# Power.net
KiCad netlist of a schematic drawn in Altium Designer
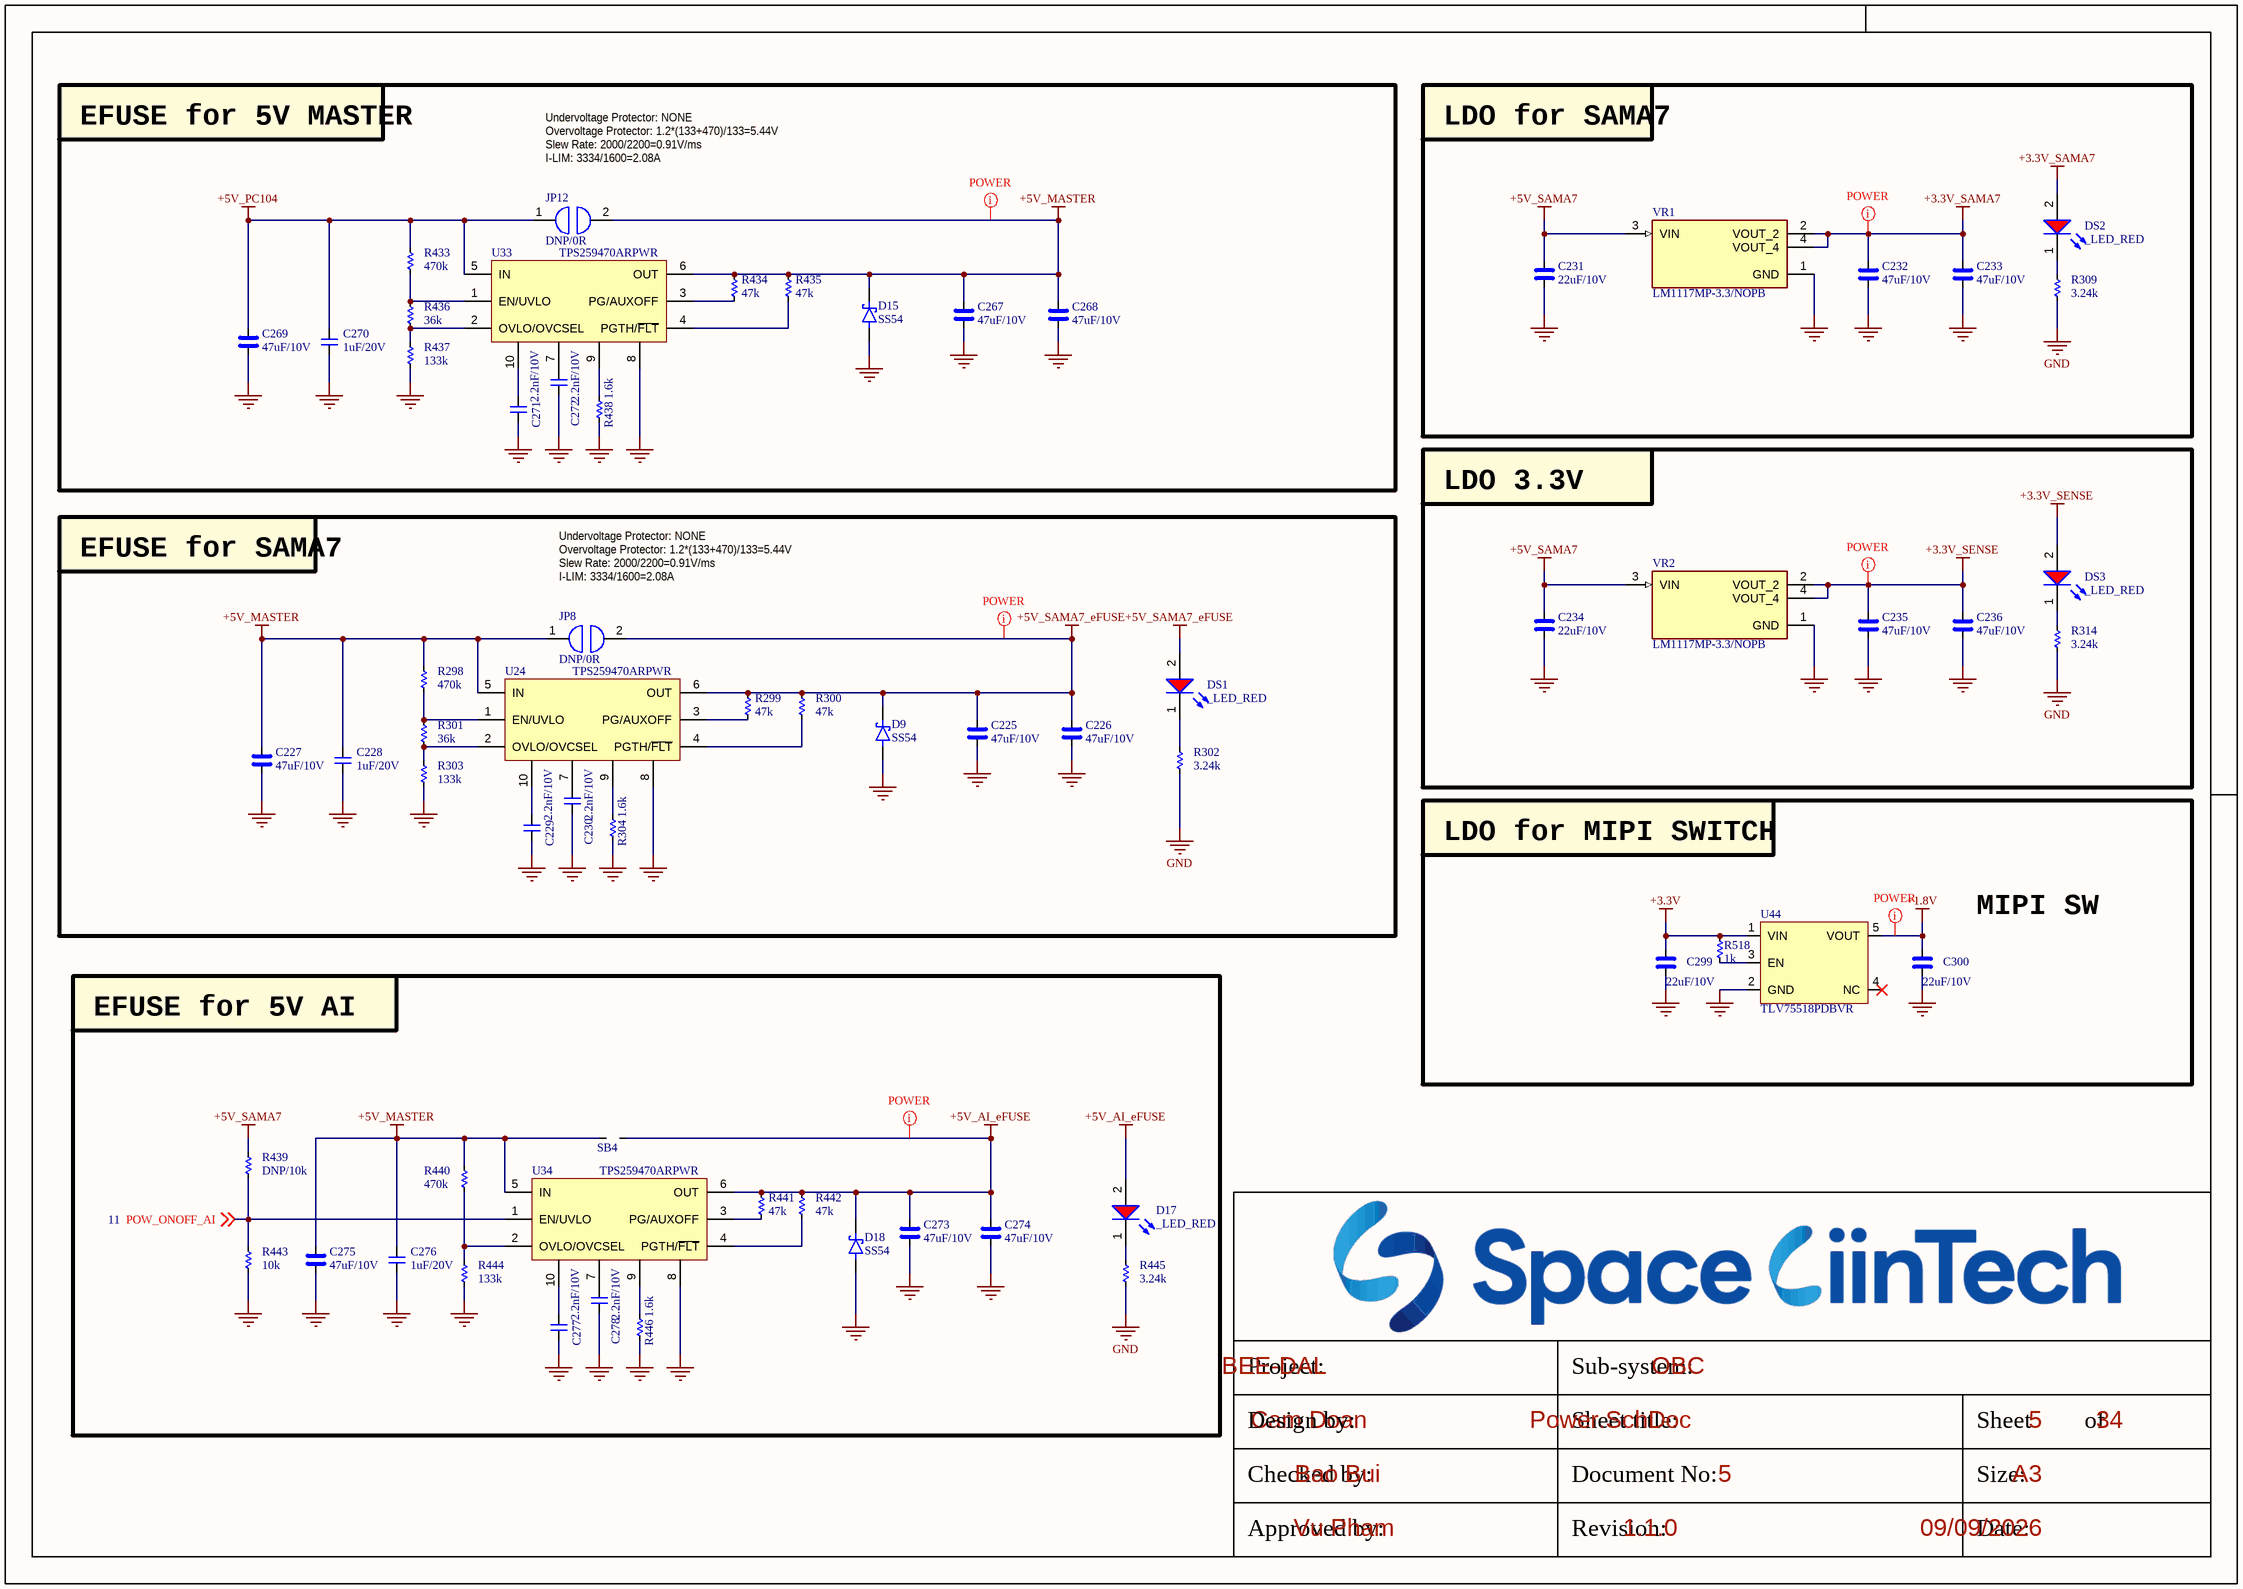
[diagram p0: Power.SchDoc]

(export (version "E")
  (design (tool "Eeschema 10.0.6"))
  (components
    (comp (ref "C225")
      (value "47uF/10V")
      (footprint "CAP_C_3225X80")
      (description "CAP High Value")
      (libsource (lib "LABLIB") (part "_CAP_C_High_2"))
    )
    (comp (ref "C226")
      (value "47uF/10V")
      (footprint "CAP_C_3225X80")
      (description "CAP High Value")
      (libsource (lib "LABLIB") (part "_CAP_C_High_2"))
    )
    (comp (ref "C227")
      (value "47uF/10V")
      (footprint "CAP_C_3225X80")
      (description "CAP High Value")
      (libsource (lib "LABLIB") (part "_CAP_C_High_2"))
    )
    (comp (ref "C228")
      (value "1uF/20V")
      (footprint "CAP_C_1005X50_L")
      (description "CAP")
      (libsource (lib "LABLIB") (part "_CAP_C_2"))
    )
    (comp (ref "C229")
      (value "2.2nF/10V")
      (footprint "CAP_C_1005X50_L")
      (description "CAP")
      (libsource (lib "LABLIB") (part "_CAP_C_2"))
    )
    (comp (ref "C230")
      (value "2.2nF/10V")
      (footprint "CAP_C_1005X50_L")
      (description "CAP")
      (libsource (lib "LABLIB") (part "_CAP_C_2"))
    )
    (comp (ref "C231")
      (value "22uF/10V")
      (footprint "CAP_C_1608X80")
      (description "CAP High Value")
      (libsource (lib "LABLIB") (part "_CAP_C_High_2"))
    )
    (comp (ref "C232")
      (value "47uF/10V")
      (footprint "CAP_C_3225X80")
      (description "CAP High Value")
      (libsource (lib "LABLIB") (part "_CAP_C_High_2"))
    )
    (comp (ref "C233")
      (value "47uF/10V")
      (footprint "CAP_C_3225X80")
      (description "CAP High Value")
      (libsource (lib "LABLIB") (part "_CAP_C_High_2"))
    )
    (comp (ref "C234")
      (value "22uF/10V")
      (footprint "CAP_C_1608X80")
      (description "CAP High Value")
      (libsource (lib "LABLIB") (part "_CAP_C_High_2"))
    )
    (comp (ref "C235")
      (value "47uF/10V")
      (footprint "CAP_C_3225X80")
      (description "CAP High Value")
      (libsource (lib "LABLIB") (part "_CAP_C_High_2"))
    )
    (comp (ref "C236")
      (value "47uF/10V")
      (footprint "CAP_C_3225X80")
      (description "CAP High Value")
      (libsource (lib "LABLIB") (part "_CAP_C_High_2"))
    )
    (comp (ref "C267")
      (value "47uF/10V")
      (footprint "CAP_C_3225X80")
      (description "CAP High Value")
      (libsource (lib "LABLIB") (part "_CAP_C_High_2"))
    )
    (comp (ref "C268")
      (value "47uF/10V")
      (footprint "CAP_C_3225X80")
      (description "CAP High Value")
      (libsource (lib "LABLIB") (part "_CAP_C_High_2"))
    )
    (comp (ref "C269")
      (value "47uF/10V")
      (footprint "CAP_C_3225X80")
      (description "CAP High Value")
      (libsource (lib "LABLIB") (part "_CAP_C_High_2"))
    )
    (comp (ref "C270")
      (value "1uF/20V")
      (footprint "CAP_C_1005X50_L")
      (description "CAP")
      (libsource (lib "LABLIB") (part "_CAP_C_2"))
    )
    (comp (ref "C271")
      (value "2.2nF/10V")
      (footprint "CAP_C_1005X50_L")
      (description "CAP")
      (libsource (lib "LABLIB") (part "_CAP_C_2"))
    )
    (comp (ref "C272")
      (value "2.2nF/10V")
      (footprint "CAP_C_1005X50_L")
      (description "CAP")
      (libsource (lib "LABLIB") (part "_CAP_C_2"))
    )
    (comp (ref "C273")
      (value "47uF/10V")
      (footprint "CAP_C_3225X80")
      (description "CAP CHIP High Value")
      (libsource (lib "IFBschelib") (part "_CAP_C_High_2"))
    )
    (comp (ref "C274")
      (value "47uF/10V")
      (footprint "CAP_C_3225X80")
      (description "CAP CHIP High Value")
      (libsource (lib "IFBschelib") (part "_CAP_C_High_2"))
    )
    (comp (ref "C275")
      (value "47uF/10V")
      (footprint "CAP_C_3225X80")
      (description "CAP CHIP High Value")
      (libsource (lib "IFBschelib") (part "_CAP_C_High_2"))
    )
    (comp (ref "C276")
      (value "1uF/20V")
      (footprint "CAP_C_1005X50_L")
      (description "CAP CHIP")
      (libsource (lib "IFBschelib") (part "_CAP_C_2"))
    )
    (comp (ref "C277")
      (value "2.2nF/10V")
      (footprint "CAP_C_1005X50_L")
      (description "CAP CHIP")
      (libsource (lib "IFBschelib") (part "_CAP_C_2"))
    )
    (comp (ref "C278")
      (value "2.2nF/10V")
      (footprint "CAP_C_1005X50_L")
      (description "CAP CHIP")
      (libsource (lib "IFBschelib") (part "_CAP_C_2"))
    )
    (comp (ref "C299")
      (value "22uF/10V")
      (footprint "CAP_C_1608X80")
      (description "CAP CHIP High Value")
      (libsource (lib "LABLIB") (part "_CAP_C_High_2"))
    )
    (comp (ref "C300")
      (value "22uF/10V")
      (footprint "CAP_C_1608X80")
      (description "CAP CHIP High Value")
      (libsource (lib "LABLIB") (part "_CAP_C_High_2"))
    )
    (comp (ref "D9")
      (value "SS54")
      (footprint "DO-214AC_SMA")
      (description "DIODE SCHOTTKY")
      (libsource (lib "LABLIB") (part "DIODE SCHOTTKY"))
    )
    (comp (ref "D15")
      (value "SS54")
      (footprint "DO-214AC_SMA")
      (description "DIODE SCHOTTKY")
      (libsource (lib "LABLIB") (part "DIODE SCHOTTKY"))
    )
    (comp (ref "D17")
      (value "_LED_RED")
      (footprint "LED_0603")
      (description "LED RED CLEAR 0603 SMD")
      (libsource (lib "IFBschelib") (part "LED_RED"))
    )
    (comp (ref "D18")
      (value "SS54")
      (footprint "DO-214AC_SMA")
      (description "DIODE SCHOTTKY")
      (libsource (lib "LABLIB") (part "DIODE SCHOTTKY"))
    )
    (comp (ref "DS1") (value "_LED_RED") (footprint "LED_0603") (libsource (lib "LABLIB") (part "_LED_RED")))
    (comp (ref "DS2") (value "_LED_RED") (footprint "LED_0603") (libsource (lib "LABLIB") (part "_LED_RED")))
    (comp (ref "DS3") (value "_LED_RED") (footprint "LED_0603") (libsource (lib "LABLIB") (part "_LED_RED")))
    (comp (ref "JP8") (value "DNP/0R") (footprint "JUMPER_1608") (libsource (lib "EXP_V1") (part "JUMPER")))
    (comp (ref "JP12") (value "DNP/0R") (footprint "JUMPER_1608") (libsource (lib "EXP_V1") (part "JUMPER")))
    (comp (ref "R298")
      (value "470k")
      (footprint "RES_C_1005x30_L")
      (description "RES")
      (libsource (lib "LABLIB") (part "_RES_B_2"))
    )
    (comp (ref "R299")
      (value "47k")
      (footprint "RES_C_1005x30_L")
      (description "RES")
      (libsource (lib "LABLIB") (part "_RES_B_2"))
    )
    (comp (ref "R300")
      (value "47k")
      (footprint "RES_C_1005x30_L")
      (description "RES")
      (libsource (lib "LABLIB") (part "_RES_B_2"))
    )
    (comp (ref "R301")
      (value "36k")
      (footprint "RES_C_1005x30_L")
      (description "RES")
      (libsource (lib "LABLIB") (part "_RES_B_2"))
    )
    (comp (ref "R302")
      (value "3.24k")
      (footprint "RES_C_1005x30_L")
      (description "RES")
      (libsource (lib "LABLIB") (part "_RES_B_2"))
    )
    (comp (ref "R303")
      (value "133k")
      (footprint "RES_C_1005x30_L")
      (description "RES")
      (libsource (lib "LABLIB") (part "_RES_B_2"))
    )
    (comp (ref "R304")
      (value "1.6k")
      (footprint "RES_C_1005x30_L")
      (description "RES")
      (libsource (lib "LABLIB") (part "_RES_B_2"))
    )
    (comp (ref "R309")
      (value "3.24k")
      (footprint "RES_C_1005x30_L")
      (description "RES")
      (libsource (lib "LABLIB") (part "_RES_B_2"))
    )
    (comp (ref "R314")
      (value "3.24k")
      (footprint "RES_C_1005x30_L")
      (description "RES")
      (libsource (lib "LABLIB") (part "_RES_B_2"))
    )
    (comp (ref "R433")
      (value "470k")
      (footprint "RES_C_1005x30_L")
      (description "RES")
      (libsource (lib "LABLIB") (part "_RES_B_2"))
    )
    (comp (ref "R434")
      (value "47k")
      (footprint "RES_C_1005x30_L")
      (description "RES")
      (libsource (lib "LABLIB") (part "_RES_B_2"))
    )
    (comp (ref "R435")
      (value "47k")
      (footprint "RES_C_1005x30_L")
      (description "RES")
      (libsource (lib "LABLIB") (part "_RES_B_2"))
    )
    (comp (ref "R436")
      (value "36k")
      (footprint "RES_C_1005x30_L")
      (description "RES")
      (libsource (lib "LABLIB") (part "_RES_B_2"))
    )
    (comp (ref "R437")
      (value "133k")
      (footprint "RES_C_1005x30_L")
      (description "RES")
      (libsource (lib "LABLIB") (part "_RES_B_2"))
    )
    (comp (ref "R438")
      (value "1.6k")
      (footprint "RES_C_1005x30_L")
      (description "RES")
      (libsource (lib "LABLIB") (part "_RES_B_2"))
    )
    (comp (ref "R439")
      (value "DNP/10k")
      (footprint "RES_C_1005x30_L")
      (description "RES")
      (libsource (lib "LABLIB") (part "_RES_B_2"))
    )
    (comp (ref "R440")
      (value "470k")
      (footprint "RES_C_1005x30_L")
      (description "RES")
      (libsource (lib "LABLIB") (part "_RES_B_2"))
    )
    (comp (ref "R441")
      (value "47k")
      (footprint "RES_C_1005x30_L")
      (description "RES")
      (libsource (lib "IFBschelib") (part "_RES_B_2"))
    )
    (comp (ref "R442")
      (value "47k")
      (footprint "RES_C_1005x30_L")
      (description "RES")
      (libsource (lib "IFBschelib") (part "_RES_B_2"))
    )
    (comp (ref "R443")
      (value "10k")
      (footprint "RES_C_1005x30_L")
      (description "RES")
      (libsource (lib "LABLIB") (part "_RES_B_2"))
    )
    (comp (ref "R444")
      (value "133k")
      (footprint "RES_C_1005x30_L")
      (description "RES")
      (libsource (lib "LABLIB") (part "_RES_B_2"))
    )
    (comp (ref "R445")
      (value "3.24k")
      (footprint "RES_C_1005x30_L")
      (description "RES")
      (libsource (lib "IFBschelib") (part "_RES_B_2"))
    )
    (comp (ref "R446")
      (value "1.6k")
      (footprint "RES_C_1005x30_L")
      (description "RES")
      (libsource (lib "IFBschelib") (part "_RES_B_2"))
    )
    (comp (ref "R518")
      (value "1k")
      (footprint "RES_C_1005x30_L")
      (description "RES")
      (libsource (lib "LABLIB") (part "_RES_B_2"))
    )
    (comp (ref "SB4")
      (value "JUMPER")
      (footprint "JUMPER_1608")
      (libsource (lib "IFBschelib") (part "JUMPER"))
    )
    (comp (ref "U24")
      (value "TPS259470ARPWR")
      (footprint "VQFN-HR-10")
      (libsource (lib "EXP_HW_V3") (part "TPS259470ARPWR"))
    )
    (comp (ref "U33")
      (value "TPS259470ARPWR")
      (footprint "VQFN-HR-10")
      (libsource (lib "EXP_HW_V3") (part "TPS259470ARPWR"))
    )
    (comp (ref "U34")
      (value "TPS259470ARPWR")
      (footprint "VQFN-HR-10")
      (libsource (lib "IFBschelib") (part "TPS259470ARPWR"))
    )
    (comp (ref "U44")
      (value "TLV75518PDBVR")
      (footprint "SOT25")
      (libsource (lib "CAMERA_SchLib") (part "IC_POWER_AP7347DQ"))
    )
    (comp (ref "VR1")
      (value "LM1117MP-3.3/NOPB")
      (footprint "VREG_LM1117MP-3.3/NOPB")
      (description "800-mA 15-V linear voltage regulator")
      (fields (field (name "MF") "Texas Instruments"))
      (libsource (lib "LABLIB") (part "LM1117MP-3.3/NOPB"))
    )
    (comp (ref "VR2")
      (value "LM1117MP-3.3/NOPB")
      (footprint "VREG_LM1117MP-3.3/NOPB")
      (description "800-mA 15-V linear voltage regulator")
      (fields (field (name "MF") "Texas Instruments"))
      (libsource (lib "LABLIB") (part "LM1117MP-3.3/NOPB"))
    )
  )
  (nets
    (net (code "1") (name "+1.8V") (class "Default")
      (node (ref "C300") (pin "1") (pinfunction "1_1") (pintype "passive"))
      (node (ref "U44") (pin "5") (pinfunction "VOUT_5") (pintype "passive"))
    )
    (net (code "2") (name "+3.3V") (class "Default")
      (node (ref "C299") (pin "1") (pinfunction "1_1") (pintype "passive"))
      (node (ref "R518") (pin "2") (pinfunction "2_2") (pintype "passive"))
      (node (ref "U44") (pin "1") (pinfunction "VIN_1") (pintype "passive"))
    )
    (net (code "3") (name "+3.3V_SAMA7") (class "Default")
      (node (ref "C232") (pin "2") (pinfunction "2_2") (pintype "passive"))
      (node (ref "C233") (pin "2") (pinfunction "2_2") (pintype "passive"))
      (node (ref "DS2") (pin "2") (pinfunction "A_2") (pintype "passive"))
      (node (ref "VR1") (pin "2") (pinfunction "VOUT_2_2") (pintype "power_in"))
      (node (ref "VR1") (pin "4") (pinfunction "VOUT_4_4") (pintype "power_in"))
    )
    (net (code "4") (name "+3.3V_SENSE") (class "Default")
      (node (ref "C235") (pin "2") (pinfunction "2_2") (pintype "passive"))
      (node (ref "C236") (pin "2") (pinfunction "2_2") (pintype "passive"))
      (node (ref "DS3") (pin "2") (pinfunction "A_2") (pintype "passive"))
      (node (ref "VR2") (pin "2") (pinfunction "VOUT_2_2") (pintype "power_in"))
      (node (ref "VR2") (pin "4") (pinfunction "VOUT_4_4") (pintype "power_in"))
    )
    (net (code "5") (name "+5V_AI_eFUSE") (class "Default")
      (node (ref "C273") (pin "2") (pinfunction "2_2") (pintype "passive"))
      (node (ref "C274") (pin "2") (pinfunction "2_2") (pintype "passive"))
      (node (ref "D17") (pin "2") (pinfunction "A_2") (pintype "passive"))
      (node (ref "D18") (pin "1") (pinfunction "K_1") (pintype "passive"))
      (node (ref "R441") (pin "2") (pinfunction "2_2") (pintype "passive"))
      (node (ref "R442") (pin "2") (pinfunction "2_2") (pintype "passive"))
      (node (ref "SB4") (pin "2") (pinfunction "2_2") (pintype "passive"))
      (node (ref "U34") (pin "6") (pinfunction "OUT_6") (pintype "passive"))
    )
    (net (code "6") (name "+5V_MASTER") (class "Default")
      (node (ref "C227") (pin "2") (pinfunction "2_2") (pintype "passive"))
      (node (ref "C228") (pin "2") (pinfunction "2_2") (pintype "passive"))
      (node (ref "C267") (pin "2") (pinfunction "2_2") (pintype "passive"))
      (node (ref "C268") (pin "2") (pinfunction "2_2") (pintype "passive"))
      (node (ref "C275") (pin "2") (pinfunction "2_2") (pintype "passive"))
      (node (ref "C276") (pin "2") (pinfunction "2_2") (pintype "passive"))
      (node (ref "D15") (pin "1") (pinfunction "K_1") (pintype "passive"))
      (node (ref "JP12") (pin "2") (pinfunction "2_2") (pintype "passive"))
      (node (ref "JP8") (pin "1") (pinfunction "1_1") (pintype "passive"))
      (node (ref "R298") (pin "2") (pinfunction "2_2") (pintype "passive"))
      (node (ref "R434") (pin "2") (pinfunction "2_2") (pintype "passive"))
      (node (ref "R435") (pin "2") (pinfunction "2_2") (pintype "passive"))
      (node (ref "R440") (pin "2") (pinfunction "2_2") (pintype "passive"))
      (node (ref "SB4") (pin "1") (pinfunction "1_1") (pintype "passive"))
      (node (ref "U24") (pin "5") (pinfunction "IN_5") (pintype "passive"))
      (node (ref "U33") (pin "6") (pinfunction "OUT_6") (pintype "passive"))
      (node (ref "U34") (pin "5") (pinfunction "IN_5") (pintype "passive"))
    )
    (net (code "7") (name "+5V_PC104") (class "Default")
      (node (ref "C269") (pin "2") (pinfunction "2_2") (pintype "passive"))
      (node (ref "C270") (pin "2") (pinfunction "2_2") (pintype "passive"))
      (node (ref "JP12") (pin "1") (pinfunction "1_1") (pintype "passive"))
      (node (ref "R433") (pin "2") (pinfunction "2_2") (pintype "passive"))
      (node (ref "U33") (pin "5") (pinfunction "IN_5") (pintype "passive"))
    )
    (net (code "8") (name "+5V_SAMA7") (class "Default")
      (node (ref "C231") (pin "1") (pinfunction "1_1") (pintype "passive"))
      (node (ref "C234") (pin "1") (pinfunction "1_1") (pintype "passive"))
      (node (ref "R439") (pin "1") (pinfunction "1_1") (pintype "passive"))
      (node (ref "VR1") (pin "3") (pinfunction "VIN_3") (pintype "input"))
      (node (ref "VR2") (pin "3") (pinfunction "VIN_3") (pintype "input"))
    )
    (net (code "9") (name "+5V_SAMA7_eFUSE") (class "Default")
      (node (ref "C225") (pin "2") (pinfunction "2_2") (pintype "passive"))
      (node (ref "C226") (pin "2") (pinfunction "2_2") (pintype "passive"))
      (node (ref "D9") (pin "1") (pinfunction "K_1") (pintype "passive"))
      (node (ref "DS1") (pin "2") (pinfunction "A_2") (pintype "passive"))
      (node (ref "JP8") (pin "2") (pinfunction "2_2") (pintype "passive"))
      (node (ref "R299") (pin "2") (pinfunction "2_2") (pintype "passive"))
      (node (ref "R300") (pin "2") (pinfunction "2_2") (pintype "passive"))
      (node (ref "U24") (pin "6") (pinfunction "OUT_6") (pintype "passive"))
    )
    (net (code "10") (name "GND") (class "Default")
      (node (ref "C225") (pin "1") (pinfunction "1_1") (pintype "passive"))
      (node (ref "C226") (pin "1") (pinfunction "1_1") (pintype "passive"))
      (node (ref "C227") (pin "1") (pinfunction "1_1") (pintype "passive"))
      (node (ref "C228") (pin "1") (pinfunction "1_1") (pintype "passive"))
      (node (ref "C229") (pin "1") (pinfunction "1_1") (pintype "passive"))
      (node (ref "C230") (pin "1") (pinfunction "1_1") (pintype "passive"))
      (node (ref "C231") (pin "2") (pinfunction "2_2") (pintype "passive"))
      (node (ref "C232") (pin "1") (pinfunction "1_1") (pintype "passive"))
      (node (ref "C233") (pin "1") (pinfunction "1_1") (pintype "passive"))
      (node (ref "C234") (pin "2") (pinfunction "2_2") (pintype "passive"))
      (node (ref "C235") (pin "1") (pinfunction "1_1") (pintype "passive"))
      (node (ref "C236") (pin "1") (pinfunction "1_1") (pintype "passive"))
      (node (ref "C267") (pin "1") (pinfunction "1_1") (pintype "passive"))
      (node (ref "C268") (pin "1") (pinfunction "1_1") (pintype "passive"))
      (node (ref "C269") (pin "1") (pinfunction "1_1") (pintype "passive"))
      (node (ref "C270") (pin "1") (pinfunction "1_1") (pintype "passive"))
      (node (ref "C271") (pin "1") (pinfunction "1_1") (pintype "passive"))
      (node (ref "C272") (pin "1") (pinfunction "1_1") (pintype "passive"))
      (node (ref "C273") (pin "1") (pinfunction "1_1") (pintype "passive"))
      (node (ref "C274") (pin "1") (pinfunction "1_1") (pintype "passive"))
      (node (ref "C275") (pin "1") (pinfunction "1_1") (pintype "passive"))
      (node (ref "C276") (pin "1") (pinfunction "1_1") (pintype "passive"))
      (node (ref "C277") (pin "1") (pinfunction "1_1") (pintype "passive"))
      (node (ref "C278") (pin "1") (pinfunction "1_1") (pintype "passive"))
      (node (ref "C299") (pin "2") (pinfunction "2_2") (pintype "passive"))
      (node (ref "C300") (pin "2") (pinfunction "2_2") (pintype "passive"))
      (node (ref "D15") (pin "2") (pinfunction "A_2") (pintype "passive"))
      (node (ref "D18") (pin "2") (pinfunction "A_2") (pintype "passive"))
      (node (ref "D9") (pin "2") (pinfunction "A_2") (pintype "passive"))
      (node (ref "R302") (pin "1") (pinfunction "1_1") (pintype "passive"))
      (node (ref "R303") (pin "1") (pinfunction "1_1") (pintype "passive"))
      (node (ref "R304") (pin "1") (pinfunction "1_1") (pintype "passive"))
      (node (ref "R309") (pin "1") (pinfunction "1_1") (pintype "passive"))
      (node (ref "R314") (pin "1") (pinfunction "1_1") (pintype "passive"))
      (node (ref "R437") (pin "1") (pinfunction "1_1") (pintype "passive"))
      (node (ref "R438") (pin "1") (pinfunction "1_1") (pintype "passive"))
      (node (ref "R443") (pin "2") (pinfunction "2_2") (pintype "passive"))
      (node (ref "R444") (pin "1") (pinfunction "1_1") (pintype "passive"))
      (node (ref "R445") (pin "1") (pinfunction "1_1") (pintype "passive"))
      (node (ref "R446") (pin "1") (pinfunction "1_1") (pintype "passive"))
      (node (ref "U24") (pin "8") (pinfunction "8_8") (pintype "passive"))
      (node (ref "U33") (pin "8") (pinfunction "8_8") (pintype "passive"))
      (node (ref "U34") (pin "8") (pinfunction "8_8") (pintype "passive"))
      (node (ref "U44") (pin "2") (pinfunction "GND_2") (pintype "passive"))
      (node (ref "VR1") (pin "1") (pinfunction "GND_1") (pintype "power_in"))
      (node (ref "VR2") (pin "1") (pinfunction "GND_1") (pintype "power_in"))
    )
    (net (code "11") (name "Net-(C229-Pad2)") (class "Default")
      (node (ref "C229") (pin "2") (pinfunction "2_2") (pintype "passive"))
      (node (ref "U24") (pin "10") (pinfunction "10_10") (pintype "passive"))
    )
    (net (code "12") (name "Net-(C230-Pad2)") (class "Default")
      (node (ref "C230") (pin "2") (pinfunction "2_2") (pintype "passive"))
      (node (ref "U24") (pin "7") (pinfunction "7_7") (pintype "passive"))
    )
    (net (code "13") (name "Net-(C271-Pad2)") (class "Default")
      (node (ref "C271") (pin "2") (pinfunction "2_2") (pintype "passive"))
      (node (ref "U33") (pin "10") (pinfunction "10_10") (pintype "passive"))
    )
    (net (code "14") (name "Net-(C272-Pad2)") (class "Default")
      (node (ref "C272") (pin "2") (pinfunction "2_2") (pintype "passive"))
      (node (ref "U33") (pin "7") (pinfunction "7_7") (pintype "passive"))
    )
    (net (code "15") (name "Net-(C277-Pad2)") (class "Default")
      (node (ref "C277") (pin "2") (pinfunction "2_2") (pintype "passive"))
      (node (ref "U34") (pin "10") (pinfunction "10_10") (pintype "passive"))
    )
    (net (code "16") (name "Net-(C278-Pad2)") (class "Default")
      (node (ref "C278") (pin "2") (pinfunction "2_2") (pintype "passive"))
      (node (ref "U34") (pin "7") (pinfunction "7_7") (pintype "passive"))
    )
    (net (code "17") (name "Net-(D17-K)") (class "Default")
      (node (ref "D17") (pin "1") (pinfunction "K_1") (pintype "passive"))
      (node (ref "R445") (pin "2") (pinfunction "2_2") (pintype "passive"))
    )
    (net (code "18") (name "Net-(DS1-K)") (class "Default")
      (node (ref "DS1") (pin "1") (pinfunction "K_1") (pintype "passive"))
      (node (ref "R302") (pin "2") (pinfunction "2_2") (pintype "passive"))
    )
    (net (code "19") (name "Net-(DS2-K)") (class "Default")
      (node (ref "DS2") (pin "1") (pinfunction "K_1") (pintype "passive"))
      (node (ref "R309") (pin "2") (pinfunction "2_2") (pintype "passive"))
    )
    (net (code "20") (name "Net-(DS3-K)") (class "Default")
      (node (ref "DS3") (pin "1") (pinfunction "K_1") (pintype "passive"))
      (node (ref "R314") (pin "2") (pinfunction "2_2") (pintype "passive"))
    )
    (net (code "21") (name "Net-(R304-Pad2)") (class "Default")
      (node (ref "R304") (pin "2") (pinfunction "2_2") (pintype "passive"))
      (node (ref "U24") (pin "9") (pinfunction "9_9") (pintype "passive"))
    )
    (net (code "22") (name "Net-(R438-Pad2)") (class "Default")
      (node (ref "R438") (pin "2") (pinfunction "2_2") (pintype "passive"))
      (node (ref "U33") (pin "9") (pinfunction "9_9") (pintype "passive"))
    )
    (net (code "23") (name "Net-(R446-Pad2)") (class "Default")
      (node (ref "R446") (pin "2") (pinfunction "2_2") (pintype "passive"))
      (node (ref "U34") (pin "9") (pinfunction "9_9") (pintype "passive"))
    )
    (net (code "24") (name "Net-(U24-EN{slash}UVLO)") (class "Default")
      (node (ref "R298") (pin "1") (pinfunction "1_1") (pintype "passive"))
      (node (ref "R301") (pin "2") (pinfunction "2_2") (pintype "passive"))
      (node (ref "U24") (pin "1") (pinfunction "EN/UVLO_1") (pintype "passive"))
    )
    (net (code "25") (name "Net-(U24-OVLO{slash}OVCSEL)") (class "Default")
      (node (ref "R301") (pin "1") (pinfunction "1_1") (pintype "passive"))
      (node (ref "R303") (pin "2") (pinfunction "2_2") (pintype "passive"))
      (node (ref "U24") (pin "2") (pinfunction "OVLO/OVCSEL_2") (pintype "passive"))
    )
    (net (code "26") (name "Net-(U24-PGTH{slash}~{FLT})") (class "Default")
      (node (ref "R300") (pin "1") (pinfunction "1_1") (pintype "passive"))
      (node (ref "U24") (pin "4") (pinfunction "PGTH/~{FLT}_4") (pintype "passive"))
    )
    (net (code "27") (name "Net-(U24-PG{slash}AUXOFF)") (class "Default")
      (node (ref "R299") (pin "1") (pinfunction "1_1") (pintype "passive"))
      (node (ref "U24") (pin "3") (pinfunction "PG/AUXOFF_3") (pintype "passive"))
    )
    (net (code "28") (name "Net-(U33-EN{slash}UVLO)") (class "Default")
      (node (ref "R433") (pin "1") (pinfunction "1_1") (pintype "passive"))
      (node (ref "R436") (pin "2") (pinfunction "2_2") (pintype "passive"))
      (node (ref "U33") (pin "1") (pinfunction "EN/UVLO_1") (pintype "passive"))
    )
    (net (code "29") (name "Net-(U33-OVLO{slash}OVCSEL)") (class "Default")
      (node (ref "R436") (pin "1") (pinfunction "1_1") (pintype "passive"))
      (node (ref "R437") (pin "2") (pinfunction "2_2") (pintype "passive"))
      (node (ref "U33") (pin "2") (pinfunction "OVLO/OVCSEL_2") (pintype "passive"))
    )
    (net (code "30") (name "Net-(U33-PGTH{slash}~{FLT})") (class "Default")
      (node (ref "R435") (pin "1") (pinfunction "1_1") (pintype "passive"))
      (node (ref "U33") (pin "4") (pinfunction "PGTH/~{FLT}_4") (pintype "passive"))
    )
    (net (code "31") (name "Net-(U33-PG{slash}AUXOFF)") (class "Default")
      (node (ref "R434") (pin "1") (pinfunction "1_1") (pintype "passive"))
      (node (ref "U33") (pin "3") (pinfunction "PG/AUXOFF_3") (pintype "passive"))
    )
    (net (code "32") (name "Net-(U34-OVLO{slash}OVCSEL)") (class "Default")
      (node (ref "R440") (pin "1") (pinfunction "1_1") (pintype "passive"))
      (node (ref "R444") (pin "2") (pinfunction "2_2") (pintype "passive"))
      (node (ref "U34") (pin "2") (pinfunction "OVLO/OVCSEL_2") (pintype "passive"))
    )
    (net (code "33") (name "Net-(U34-PGTH{slash}~{FLT})") (class "Default")
      (node (ref "R442") (pin "1") (pinfunction "1_1") (pintype "passive"))
      (node (ref "U34") (pin "4") (pinfunction "PGTH/~{FLT}_4") (pintype "passive"))
    )
    (net (code "34") (name "Net-(U34-PG{slash}AUXOFF)") (class "Default")
      (node (ref "R441") (pin "1") (pinfunction "1_1") (pintype "passive"))
      (node (ref "U34") (pin "3") (pinfunction "PG/AUXOFF_3") (pintype "passive"))
    )
    (net (code "35") (name "Net-(U44-EN)") (class "Default")
      (node (ref "R518") (pin "1") (pinfunction "1_1") (pintype "passive"))
      (node (ref "U44") (pin "3") (pinfunction "EN_3") (pintype "passive"))
    )
    (net (code "36") (name "POW_ONOFF_AI") (class "Default")
      (node (ref "R439") (pin "2") (pinfunction "2_2") (pintype "passive"))
      (node (ref "R443") (pin "1") (pinfunction "1_1") (pintype "passive"))
      (node (ref "U34") (pin "1") (pinfunction "EN/UVLO_1") (pintype "passive"))
    )
    (net (code "37") (name "unconnected-(U44-NC-Pad4)") (class "Default")
      (node (ref "U44") (pin "4") (pinfunction "NC_4") (pintype "passive+no_connect"))
    )
  )
)
